# BANK16.net
KiCad netlist of a schematic drawn in Altium Designer
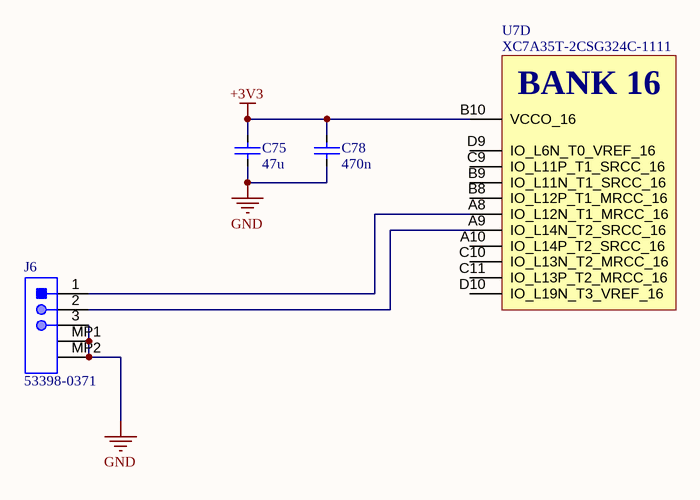
[diagram p0: BANK16.SchDoc]

(export (version "E")
  (design (tool "Eeschema 10.0.6"))
  (components
    (comp (ref "C75")
      (value "47u")
      (footprint "FP-C2012-125-0_2-IPC_C")
      (description "47μF ±20% 10V X5R SMD 0805 Multilayer Ceramic Capacitors")
      (fields (field (name "VOLTAGE") "10V") (field (name "TOLERANCE") "20%"))
      (libsource (lib "Schlib1") (part "C2012X5R1A476M125AC"))
    )
    (comp (ref "C78")
      (value "470n")
      (footprint "pcblib1:FP-C1005-050-0_05-IPC_C")
      (description "Multilayer Ceramic Capacitors 470nF ±10% 25V X5R SMD 0402")
      (fields (field (name "VOLTAGE") "25V") (field (name "TOLERANCE") "10%"))
      (libsource (lib "Schlib1") (part "C1005X5R1E474K050BB"))
    )
    (comp (ref "J6")
      (value "53398-0371")
      (footprint "MOLX-53398-0371_V")
      (description "Male Header, Pitch 1.25 mm, 1 x 3 Position, Height 4.7 mm, -40 to 85 degC, RoHS, Tape and Reel")
      (fields (field (name "MANUFACTURER") "Molex"))
      (libsource (lib "Schlib1") (part "53398-0371"))
    )
    (comp (ref "U7")
      (value "XC7A35T-2CSG324C-1111")
      (footprint "PCBLIB1:BGA324C80P18X18_1500X1500X150")
      (description "Integrated Circuit")
      (fields
        (field (name "MANUFACTURER_PART_NUMBER") "XC7A35T-2CSG324C")
        (field (name "MOUSER PART NUMBER") "217-XC7A35T-2CSG324C")
      )
      (libsource (lib "Schlib1") (part "XC7A35T-2CSG324C-1111"))
    )
  )
  (nets
    (net (code "1") (name "+3V3") (class "Default")
      (node (ref "C75") (pin "1") (pinfunction "1_1") (pintype "passive"))
      (node (ref "C78") (pin "1") (pinfunction "1_1") (pintype "passive"))
      (node (ref "U7") (pin "B10") (pinfunction "VCCO_16_B10") (pintype "passive"))
    )
    (net (code "2") (name "GND") (class "Default")
      (node (ref "C75") (pin "2") (pinfunction "2_2") (pintype "passive"))
      (node (ref "C78") (pin "2") (pinfunction "2_2") (pintype "passive"))
      (node (ref "J6") (pin "3") (pinfunction "3_3") (pintype "passive"))
      (node (ref "J6") (pin "MP1") (pinfunction "MP1_MP1") (pintype "passive"))
      (node (ref "J6") (pin "MP2") (pinfunction "MP2_MP2") (pintype "passive"))
    )
    (net (code "3") (name "Net-(U7D-IO_L12N_T1_MRCC_16)") (class "Default")
      (node (ref "J6") (pin "1") (pinfunction "1_1") (pintype "passive"))
      (node (ref "U7") (pin "A8") (pinfunction "IO_L12N_T1_MRCC_16_A8") (pintype "passive"))
    )
    (net (code "4") (name "Net-(U7D-IO_L14N_T2_SRCC_16)") (class "Default")
      (node (ref "J6") (pin "2") (pinfunction "2_2") (pintype "passive"))
      (node (ref "U7") (pin "A9") (pinfunction "IO_L14N_T2_SRCC_16_A9") (pintype "passive"))
    )
    (net (code "5") (name "unconnected-(U7D-IO_L6N_T0_VREF_16-PadD9)") (class "Default")
      (node (ref "U7") (pin "D9") (pinfunction "IO_L6N_T0_VREF_16_D9") (pintype "passive"))
    )
    (net (code "6") (name "unconnected-(U7D-IO_L11N_T1_SRCC_16-PadB9)") (class "Default")
      (node (ref "U7") (pin "B9") (pinfunction "IO_L11N_T1_SRCC_16_B9") (pintype "passive"))
    )
    (net (code "7") (name "unconnected-(U7D-IO_L11P_T1_SRCC_16-PadC9)") (class "Default")
      (node (ref "U7") (pin "C9") (pinfunction "IO_L11P_T1_SRCC_16_C9") (pintype "passive"))
    )
    (net (code "8") (name "unconnected-(U7D-IO_L12P_T1_MRCC_16-PadB8)") (class "Default")
      (node (ref "U7") (pin "B8") (pinfunction "IO_L12P_T1_MRCC_16_B8") (pintype "passive"))
    )
    (net (code "9") (name "unconnected-(U7D-IO_L13N_T2_MRCC_16-PadC10)") (class "Default")
      (node (ref "U7") (pin "C10") (pinfunction "IO_L13N_T2_MRCC_16_C10") (pintype "passive"))
    )
    (net (code "10") (name "unconnected-(U7D-IO_L13P_T2_MRCC_16-PadC11)") (class "Default")
      (node (ref "U7") (pin "C11") (pinfunction "IO_L13P_T2_MRCC_16_C11") (pintype "passive"))
    )
    (net (code "11") (name "unconnected-(U7D-IO_L14P_T2_SRCC_16-PadA10)") (class "Default")
      (node (ref "U7") (pin "A10") (pinfunction "IO_L14P_T2_SRCC_16_A10") (pintype "passive"))
    )
    (net (code "12") (name "unconnected-(U7D-IO_L19N_T3_VREF_16-PadD10)") (class "Default")
      (node (ref "U7") (pin "D10") (pinfunction "IO_L19N_T3_VREF_16_D10") (pintype "passive"))
    )
  )
)
